# Microcontroller.net
KiCad netlist of a schematic drawn in Altium Designer
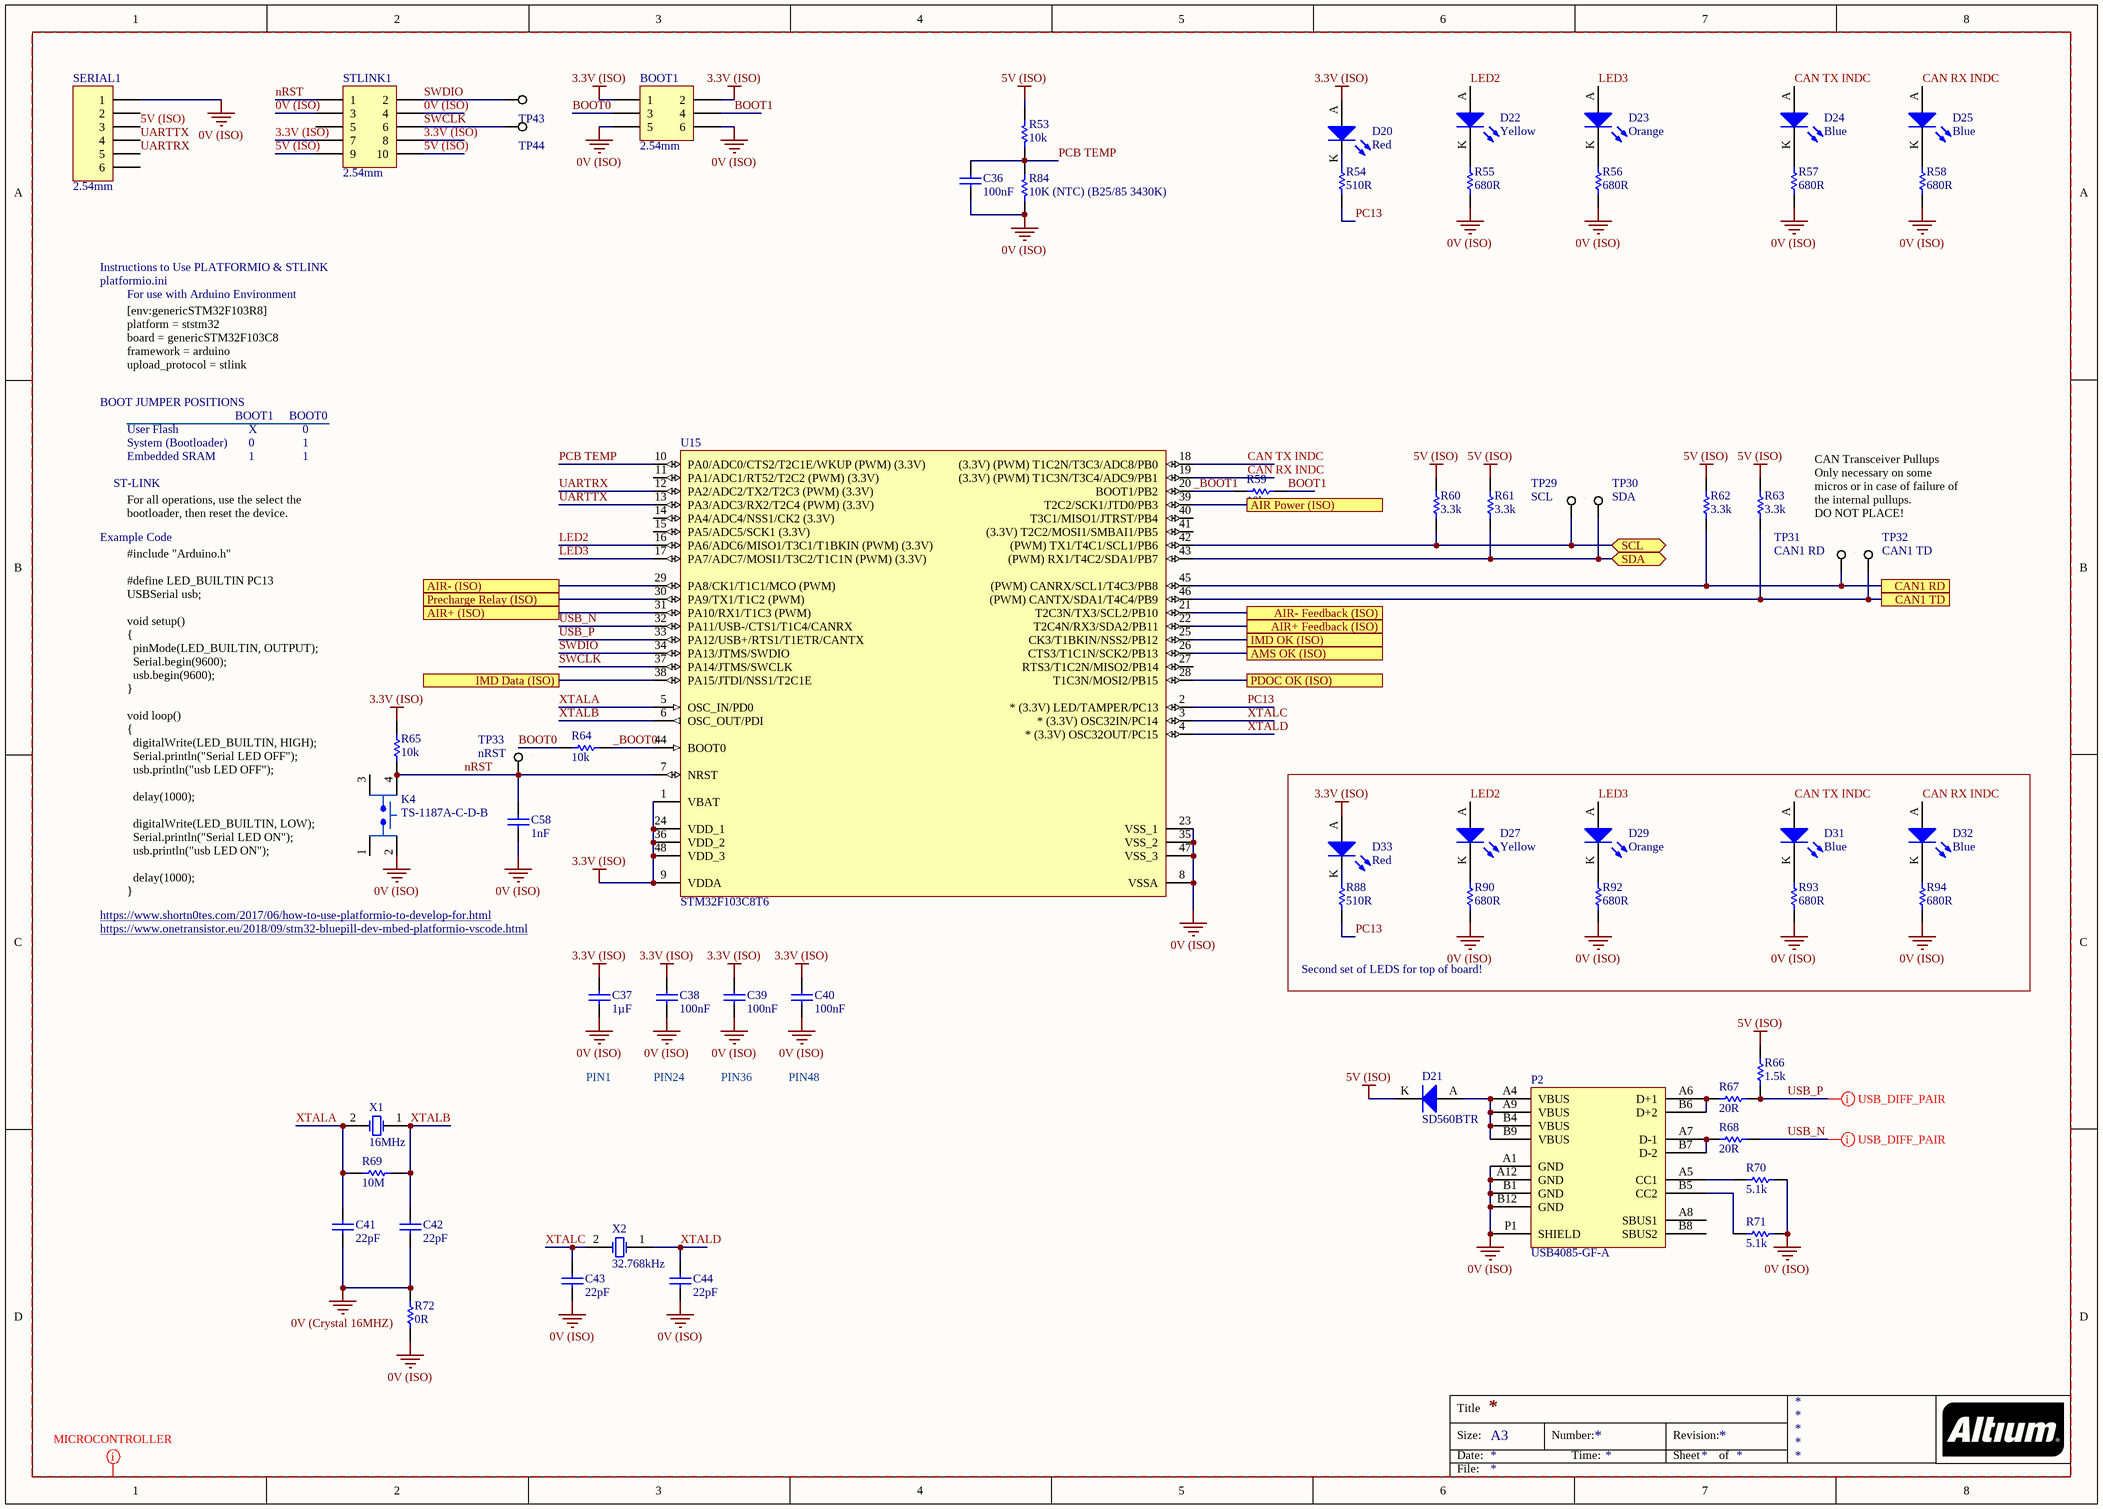
[diagram p0: Microcontroller.SchDoc]

(export (version "E")
  (design (tool "Eeschema 10.0.6"))
  (components
    (comp (ref "BOOT1")
      (value "2.54mm")
      (footprint "TH 2.54mm Header 2x3")
      (fields (field (name "PART NUMBER") "TH 2.54mm Header 2x3") (field (name "CONTACT") "NA"))
      (libsource (lib "ts_20-standard-connectors") (part "Header 2x3"))
    )
    (comp (ref "C36")
      (value "100nF")
      (footprint "0805")
      (fields
        (field (name "PART NUMBER") "GCM21BR71E104KA37L")
        (field (name "TOLERANCE") "10%")
        (field (name "MANUFACTURER") "muRata")
      )
      (libsource (lib "ts_20-standard-library") (part "Capacitor"))
    )
    (comp (ref "C37")
      (value "1µF")
      (footprint "0805")
      (fields
        (field (name "PART NUMBER") "GCM21BR71H105KA03L")
        (field (name "TOLERANCE") "±10%")
        (field (name "MANUFACTURER") "muRata")
      )
      (libsource (lib "ts_20-standard-library") (part "Capacitor"))
    )
    (comp (ref "C38")
      (value "100nF")
      (footprint "0805")
      (fields
        (field (name "PART NUMBER") "GCM21BR71H104KA37L")
        (field (name "TOLERANCE") "±10%")
        (field (name "MANUFACTURER") "muRata")
      )
      (libsource (lib "ts_20-standard-library") (part "Capacitor"))
    )
    (comp (ref "C39")
      (value "100nF")
      (footprint "0805")
      (fields
        (field (name "PART NUMBER") "GCM21BR71H104KA37L")
        (field (name "TOLERANCE") "±10%")
        (field (name "MANUFACTURER") "muRata")
      )
      (libsource (lib "ts_20-standard-library") (part "Capacitor"))
    )
    (comp (ref "C40")
      (value "100nF")
      (footprint "0805")
      (fields
        (field (name "PART NUMBER") "GCM21BR71H104KA37L")
        (field (name "TOLERANCE") "±10%")
        (field (name "MANUFACTURER") "muRata")
      )
      (libsource (lib "ts_20-standard-library") (part "Capacitor"))
    )
    (comp (ref "C41")
      (value "22pF")
      (footprint "0805")
      (fields
        (field (name "PART NUMBER") "GRM21A5C2E220JW01D")
        (field (name "TOLERANCE") "±5%")
        (field (name "MANUFACTURER") "muRata")
      )
      (libsource (lib "ts_20-standard-library") (part "Capacitor"))
    )
    (comp (ref "C42")
      (value "22pF")
      (footprint "0805")
      (fields
        (field (name "PART NUMBER") "GRM21A5C2E220JW01D")
        (field (name "TOLERANCE") "±5%")
        (field (name "MANUFACTURER") "muRata")
      )
      (libsource (lib "ts_20-standard-library") (part "Capacitor"))
    )
    (comp (ref "C43")
      (value "22pF")
      (footprint "0805")
      (fields
        (field (name "PART NUMBER") "GRM21A5C2E220JW01D")
        (field (name "TOLERANCE") "±5%")
        (field (name "MANUFACTURER") "muRata")
      )
      (libsource (lib "ts_20-standard-library") (part "Capacitor"))
    )
    (comp (ref "C44")
      (value "22pF")
      (footprint "0805")
      (fields
        (field (name "PART NUMBER") "GRM21A5C2E220JW01D")
        (field (name "TOLERANCE") "±5%")
        (field (name "MANUFACTURER") "muRata")
      )
      (libsource (lib "ts_20-standard-library") (part "Capacitor"))
    )
    (comp (ref "C58")
      (value "1nF")
      (footprint "0805")
      (fields
        (field (name "PART NUMBER") "GCM21BR71H102KA37L")
        (field (name "TOLERANCE") "10%")
        (field (name "MANUFACTURER") "muRata")
      )
      (libsource (lib "ts_20-standard-library") (part "Capacitor"))
    )
    (comp (ref "D20")
      (value "Red")
      (footprint "0805 LED")
      (description "Red LED Indication - Discrete 1.75V 0805 (2012 Metric)")
      (fields (field (name "MANUFACTURER") "ROHM Semiconductor") (field (name "PART NUMBER") "SML-210LTT86"))
      (libsource (lib "ts_20-standard-library") (part "LED"))
    )
    (comp (ref "D21")
      (value "SD560BTR")
      (footprint "SMB Diode")
      (description "1.2V_F 600V 5A SMB")
      (fields
        (field (name "MANUFACTURER") "SMC Diode Solutions")
        (field (name "DIGIKEY PART NUMBER") "1655-1530-2-ND")
      )
      (libsource (lib "ts_20-standard-library") (part "Diode"))
    )
    (comp (ref "D22")
      (value "Yellow")
      (footprint "0805 LED")
      (description "Yellow LED Indication - Discrete 1.75V 0805 (2012 Metric)")
      (fields (field (name "PART NUMBER") "SML-211YTT86") (field (name "MANUFACTURER") "ROHM Semiconductor"))
      (libsource (lib "ts_20-standard-library") (part "LED"))
    )
    (comp (ref "D23")
      (value "Orange")
      (footprint "0805 LED")
      (description "Orange LED Indication - Discrete 1.75V 0805 (2012 Metric)")
      (fields (field (name "PART NUMBER") "SML-211DTT86") (field (name "MANUFACTURER") "ROHM Semiconductor"))
      (libsource (lib "ts_20-standard-library") (part "LED"))
    )
    (comp (ref "D24")
      (value "Blue")
      (footprint "0805 LED")
      (description "LED BLUE CLEAR 2012 SMD")
      (fields
        (field (name "PART NUMBER") "SML-MN2BCTT86C")
        (field (name "MANUFACTURER") "ROHM Semiconductor")
      )
      (libsource (lib "ts_20-standard-library") (part "LED"))
    )
    (comp (ref "D25")
      (value "Blue")
      (footprint "0805 LED")
      (description "LED BLUE CLEAR 2012 SMD")
      (fields
        (field (name "PART NUMBER") "SML-MN2BCTT86C")
        (field (name "MANUFACTURER") "ROHM Semiconductor")
      )
      (libsource (lib "ts_20-standard-library") (part "LED"))
    )
    (comp (ref "D27")
      (value "Yellow")
      (footprint "0805 LED")
      (description "Yellow LED Indication - Discrete 1.75V 0805 (2012 Metric)")
      (fields (field (name "PART NUMBER") "SML-211YTT86") (field (name "MANUFACTURER") "ROHM Semiconductor"))
      (libsource (lib "ts_20-standard-library") (part "LED"))
    )
    (comp (ref "D29")
      (value "Orange")
      (footprint "0805 LED")
      (description "Orange LED Indication - Discrete 1.75V 0805 (2012 Metric)")
      (fields (field (name "PART NUMBER") "SML-211DTT86") (field (name "MANUFACTURER") "ROHM Semiconductor"))
      (libsource (lib "ts_20-standard-library") (part "LED"))
    )
    (comp (ref "D31")
      (value "Blue")
      (footprint "0805 LED")
      (description "LED BLUE CLEAR 2012 SMD")
      (fields
        (field (name "PART NUMBER") "SML-MN2BCTT86C")
        (field (name "MANUFACTURER") "ROHM Semiconductor")
      )
      (libsource (lib "ts_20-standard-library") (part "LED"))
    )
    (comp (ref "D32")
      (value "Blue")
      (footprint "0805 LED")
      (description "LED BLUE CLEAR 2012 SMD")
      (fields
        (field (name "PART NUMBER") "SML-MN2BCTT86C")
        (field (name "MANUFACTURER") "ROHM Semiconductor")
      )
      (libsource (lib "ts_20-standard-library") (part "LED"))
    )
    (comp (ref "D33")
      (value "Red")
      (footprint "0805 LED")
      (description "Red LED Indication - Discrete 1.75V 0805 (2012 Metric)")
      (fields (field (name "MANUFACTURER") "ROHM Semiconductor") (field (name "PART NUMBER") "SML-210LTT86"))
      (libsource (lib "ts_20-standard-library") (part "LED"))
    )
    (comp (ref "K4")
      (value "TS-1187A-C-D-B")
      (footprint "XKB SW-4.5")
      (description "TACTILE SWITCHES SPST 5.10MM X 5.10MM 0.80MM SMD ROHS")
      (fields (field (name "MANUFACTURER") "XKB Enerprise"))
      (libsource (lib "ts_20-standard-library") (part "SPST (Mom) Push Button"))
    )
    (comp (ref "P2")
      (value "USB4085-GF-A")
      (footprint "USB4085-GF-A")
      (description "USB - C (Type - C) USB 2.0 Receptacle Connector 16 Position Through Hole, Right Angle")
      (fields (field (name "DIGIKEY PART NUMBER") "2073-USB4085-GF-ACT-ND"))
      (libsource (lib "ts_20-standard-connectors") (part "USB4085-GF-A"))
    )
    (comp (ref "R53")
      (value "10k")
      (footprint "0805")
      (fields
        (field (name "PART NUMBER") "RC0805FR0710KL")
        (field (name "MANUFACTURER") "YAGEO")
        (field (name "TOLERANCE") "0.01")
      )
      (libsource (lib "ts_20-standard-library") (part "Resistor"))
    )
    (comp (ref "R54")
      (value "510R")
      (footprint "0805")
      (fields
        (field (name "MANUFACTURER") "YAGEO")
        (field (name "PART NUMBER") "RC0805FR07510RL")
        (field (name "TOLERANCE") "0.01")
      )
      (libsource (lib "ts_20-standard-library") (part "Resistor"))
    )
    (comp (ref "R55")
      (value "680R")
      (footprint "0805")
      (fields
        (field (name "PART NUMBER") "RC0805FR07680RL")
        (field (name "MANUFACTURER") "YAGEO")
        (field (name "TOLERANCE") "0.01")
      )
      (libsource (lib "ts_20-standard-library") (part "Resistor"))
    )
    (comp (ref "R56")
      (value "680R")
      (footprint "0805")
      (fields
        (field (name "PART NUMBER") "RC0805FR07680RL")
        (field (name "MANUFACTURER") "YAGEO")
        (field (name "TOLERANCE") "0.01")
      )
      (libsource (lib "ts_20-standard-library") (part "Resistor"))
    )
    (comp (ref "R57")
      (value "680R")
      (footprint "0805")
      (fields
        (field (name "PART NUMBER") "RC0805FR07680RL")
        (field (name "MANUFACTURER") "YAGEO")
        (field (name "TOLERANCE") "0.01")
      )
      (libsource (lib "ts_20-standard-library") (part "Resistor"))
    )
    (comp (ref "R58")
      (value "680R")
      (footprint "0805")
      (fields
        (field (name "PART NUMBER") "RC0805FR07680RL")
        (field (name "MANUFACTURER") "YAGEO")
        (field (name "TOLERANCE") "0.01")
      )
      (libsource (lib "ts_20-standard-library") (part "Resistor"))
    )
    (comp (ref "R59")
      (value "10k")
      (footprint "0805")
      (fields
        (field (name "PART NUMBER") "RC0805FR0710KL")
        (field (name "MANUFACTURER") "YAGEO")
        (field (name "TOLERANCE") "0.01")
      )
      (libsource (lib "ts_20-standard-library") (part "Resistor"))
    )
    (comp (ref "R60")
      (value "3.3k")
      (footprint "0805")
      (fields
        (field (name "PART NUMBER") "RC0805FR073K3L")
        (field (name "MANUFACTURER") "YAGEO")
        (field (name "TOLERANCE") "0.01")
      )
      (libsource (lib "ts_20-standard-library") (part "Resistor"))
    )
    (comp (ref "R61")
      (value "3.3k")
      (footprint "0805")
      (fields
        (field (name "PART NUMBER") "RC0805FR073K3L")
        (field (name "MANUFACTURER") "YAGEO")
        (field (name "TOLERANCE") "0.01")
      )
      (libsource (lib "ts_20-standard-library") (part "Resistor"))
    )
    (comp (ref "R62")
      (value "3.3k")
      (footprint "0805")
      (fields
        (field (name "PART NUMBER") "RC0805FR073K3L")
        (field (name "MANUFACTURER") "YAGEO")
        (field (name "TOLERANCE") "0.01")
      )
      (libsource (lib "ts_20-standard-library") (part "Resistor"))
    )
    (comp (ref "R63")
      (value "3.3k")
      (footprint "0805")
      (fields
        (field (name "PART NUMBER") "RC0805FR073K3L")
        (field (name "MANUFACTURER") "YAGEO")
        (field (name "TOLERANCE") "0.01")
      )
      (libsource (lib "ts_20-standard-library") (part "Resistor"))
    )
    (comp (ref "R64")
      (value "10k")
      (footprint "0805")
      (fields
        (field (name "PART NUMBER") "RC0805FR0710KL")
        (field (name "MANUFACTURER") "YAGEO")
        (field (name "TOLERANCE") "0.01")
      )
      (libsource (lib "ts_20-standard-library") (part "Resistor"))
    )
    (comp (ref "R65")
      (value "10k")
      (footprint "0805")
      (fields
        (field (name "MANUFACTURER") "YAGEO")
        (field (name "PART NUMBER") "RC0805FR0710KL")
        (field (name "TOLERANCE") "0.01")
      )
      (libsource (lib "ts_20-standard-library") (part "Resistor"))
    )
    (comp (ref "R66")
      (value "1.5k")
      (footprint "0805")
      (fields
        (field (name "PART NUMBER") "RC0805FR071K5L")
        (field (name "MANUFACTURER") "YAGEO")
        (field (name "TOLERANCE") "0.01")
      )
      (libsource (lib "ts_20-standard-library") (part "Resistor"))
    )
    (comp (ref "R67")
      (value "20R")
      (footprint "0805")
      (fields
        (field (name "PART NUMBER") "RC0805FR0720RL")
        (field (name "MANUFACTURER") "YAGEO")
        (field (name "TOLERANCE") "0.01")
      )
      (libsource (lib "ts_20-standard-library") (part "Resistor"))
    )
    (comp (ref "R68")
      (value "20R")
      (footprint "0805")
      (fields
        (field (name "PART NUMBER") "RC0805FR0720RL")
        (field (name "MANUFACTURER") "YAGEO")
        (field (name "TOLERANCE") "0.01")
      )
      (libsource (lib "ts_20-standard-library") (part "Resistor"))
    )
    (comp (ref "R69")
      (value "10M")
      (footprint "0805")
      (fields
        (field (name "PART NUMBER") "RC0805FR0710ML")
        (field (name "MANUFACTURER") "YAGEO")
        (field (name "TOLERANCE") "0.01")
      )
      (libsource (lib "ts_20-standard-library") (part "Resistor"))
    )
    (comp (ref "R70")
      (value "5.1k")
      (footprint "0805")
      (fields
        (field (name "PART NUMBER") "RC0805FR075K1L")
        (field (name "MANUFACTURER") "YAGEO")
        (field (name "TOLERANCE") "0.01")
      )
      (libsource (lib "ts_20-standard-library") (part "Resistor"))
    )
    (comp (ref "R71")
      (value "5.1k")
      (footprint "0805")
      (fields
        (field (name "PART NUMBER") "RC0805FR075K1L")
        (field (name "MANUFACTURER") "YAGEO")
        (field (name "TOLERANCE") "0.01")
      )
      (libsource (lib "ts_20-standard-library") (part "Resistor"))
    )
    (comp (ref "R72")
      (value "0R")
      (footprint "0805")
      (fields
        (field (name "PART NUMBER") "RC0805FR070RL")
        (field (name "MANUFACTURER") "YAGEO")
        (field (name "TOLERANCE") "0.01")
      )
      (libsource (lib "ts_20-standard-library") (part "Resistor"))
    )
    (comp (ref "R84")
      (value "10K (NTC) (B25/85 3430K)")
      (footprint "0805")
      (fields
        (field (name "PART NUMBER") "NTCS0805E3103FLT")
        (field (name "MANUFACTURER") "Vishay Beyschlag")
        (field (name "TOLERANCE") "0.01")
      )
      (libsource (lib "ts_20-standard-library") (part "Resistor"))
    )
    (comp (ref "R88")
      (value "510R")
      (footprint "0805")
      (fields
        (field (name "MANUFACTURER") "YAGEO")
        (field (name "PART NUMBER") "RC0805FR07510RL")
        (field (name "TOLERANCE") "0.01")
      )
      (libsource (lib "ts_20-standard-library") (part "Resistor"))
    )
    (comp (ref "R90")
      (value "680R")
      (footprint "0805")
      (fields
        (field (name "PART NUMBER") "RC0805FR07680RL")
        (field (name "MANUFACTURER") "YAGEO")
        (field (name "TOLERANCE") "0.01")
      )
      (libsource (lib "ts_20-standard-library") (part "Resistor"))
    )
    (comp (ref "R92")
      (value "680R")
      (footprint "0805")
      (fields
        (field (name "PART NUMBER") "RC0805FR07680RL")
        (field (name "MANUFACTURER") "YAGEO")
        (field (name "TOLERANCE") "0.01")
      )
      (libsource (lib "ts_20-standard-library") (part "Resistor"))
    )
    (comp (ref "R93")
      (value "680R")
      (footprint "0805")
      (fields
        (field (name "PART NUMBER") "RC0805FR07680RL")
        (field (name "MANUFACTURER") "YAGEO")
        (field (name "TOLERANCE") "0.01")
      )
      (libsource (lib "ts_20-standard-library") (part "Resistor"))
    )
    (comp (ref "R94")
      (value "680R")
      (footprint "0805")
      (fields
        (field (name "PART NUMBER") "RC0805FR07680RL")
        (field (name "MANUFACTURER") "YAGEO")
        (field (name "TOLERANCE") "0.01")
      )
      (libsource (lib "ts_20-standard-library") (part "Resistor"))
    )
    (comp (ref "SERIAL1")
      (value "2.54mm")
      (footprint "TH 2.54mm Header 1x6")
      (fields (field (name "PART NUMBER") "TH 2.54mm Header 1x6") (field (name "CONTACT") "NA"))
      (libsource (lib "ts_20-standard-connectors") (part "Header 1x6"))
    )
    (comp (ref "STLINK1")
      (value "2.54mm")
      (footprint "TH 2.54mm Header 2x5")
      (fields (field (name "PART NUMBER") "TH 2.54mm Header 2x5") (field (name "CONTACT") "NA"))
      (libsource (lib "ts_20-standard-connectors") (part "Header 2x5"))
    )
    (comp (ref "TP29")
      (value "SCL")
      (footprint "SMD Test Point 1mm")
      (fields (field (name "PART NUMBER") "SMD Test Point Small") (field (name "CONTACT") "NA"))
      (libsource (lib "ts_20-standard-connectors") (part "Test Point Small"))
    )
    (comp (ref "TP30")
      (value "SDA")
      (footprint "SMD Test Point 1mm")
      (fields (field (name "PART NUMBER") "SMD Test Point Small") (field (name "CONTACT") "NA"))
      (libsource (lib "ts_20-standard-connectors") (part "Test Point Small"))
    )
    (comp (ref "TP31")
      (value "CAN1 RD")
      (footprint "SMD Test Point 1mm")
      (fields (field (name "PART NUMBER") "SMD Test Point Small") (field (name "CONTACT") "NA"))
      (libsource (lib "ts_20-standard-connectors") (part "Test Point Small"))
    )
    (comp (ref "TP32")
      (value "CAN1 TD")
      (footprint "SMD Test Point 1mm")
      (fields (field (name "PART NUMBER") "SMD Test Point Small") (field (name "CONTACT") "NA"))
      (libsource (lib "ts_20-standard-connectors") (part "Test Point Small"))
    )
    (comp (ref "TP33")
      (value "nRST")
      (footprint "SMD Test Point 1mm")
      (fields (field (name "PART NUMBER") "SMD Test Point Small") (field (name "CONTACT") "NA"))
      (libsource (lib "ts_20-standard-connectors") (part "Test Point Small"))
    )
    (comp (ref "TP43")
      (value "0mm")
      (footprint "SMD Test Point 1mm")
      (fields (field (name "PART NUMBER") "SMD Test Point Small") (field (name "CONTACT") "NA"))
      (libsource (lib "ts_20-standard-connectors") (part "Test Point Small"))
    )
    (comp (ref "TP44")
      (value "0mm")
      (footprint "SMD Test Point 1mm")
      (fields (field (name "PART NUMBER") "SMD Test Point Small") (field (name "CONTACT") "NA"))
      (libsource (lib "ts_20-standard-connectors") (part "Test Point Small"))
    )
    (comp (ref "U15")
      (value "STM32F103C8T6")
      (footprint "STM 48-LQFP")
      (description "ARM® Cortex®-M3 STM32F1 Microcontroller IC 32-Bit 72MHz 64KB (64K x 8) FLASH")
      (fields
        (field (name "MANUFACTURER") "STMicroelectronics")
        (field (name "DIGIKEY PART NUMBER") "497-6063-ND")
      )
      (libsource (lib "ts_20-standard-library") (part "STM32F103C8T6"))
    )
    (comp (ref "X1")
      (value "16MHz")
      (footprint "Abracon HC-49/US")
      (fields
        (field (name "PART NUMBER") "ABLS-16.000MHZ-B4-T")
        (field (name "MANUFACTURER") "Abracon LLC")
        (field (name "DIGIKEY PART NUMBER") "535-10226-1-ND")
      )
      (libsource (lib "ts_20-standard-library") (part "Crystal"))
    )
    (comp (ref "X2")
      (value "32.768kHz")
      (footprint "EPSON 2-SMD")
      (fields
        (field (name "PART NUMBER") "FC-135 32.7680KA-A5")
        (field (name "MANUFACTURER") "EPSON")
        (field (name "DIGIKEY PART NUMBER") "SER4103TR-ND")
      )
      (libsource (lib "ts_20-standard-library") (part "Crystal"))
    )
  )
  (nets
    (net (code "1") (name "/AIR Power (ISO)") (class "Default")
      (node (ref "U15") (pin "39") (pinfunction "T2C2/SCK1/JTD0/PB3_39") (pintype "bidirectional"))
    )
    (net (code "2") (name "/AIR+ (ISO)") (class "Default")
      (node (ref "U15") (pin "31") (pinfunction "PA10/RX1/T1C3_(PWM)_31") (pintype "bidirectional"))
    )
    (net (code "3") (name "/AIR+ Feedback (ISO)") (class "Default")
      (node (ref "U15") (pin "22") (pinfunction "T2C4N/RX3/SDA2/PB11_22") (pintype "bidirectional"))
    )
    (net (code "4") (name "/AIR- (ISO)") (class "Default")
      (node (ref "U15") (pin "29") (pinfunction "PA8/CK1/T1C1/MCO_(PWM)_29") (pintype "bidirectional"))
    )
    (net (code "5") (name "/AIR- Feedback (ISO)") (class "Default")
      (node (ref "U15") (pin "21") (pinfunction "T2C3N/TX3/SCL2/PB10_21") (pintype "bidirectional"))
    )
    (net (code "6") (name "/AMS OK (ISO)") (class "Default")
      (node (ref "U15") (pin "26") (pinfunction "CTS3/T1C1N/SCK2/PB13_26") (pintype "bidirectional"))
    )
    (net (code "7") (name "/BOOT0") (class "Default")
      (node (ref "BOOT1") (pin "3") (pinfunction "3_3") (pintype "passive"))
      (node (ref "R64") (pin "1") (pinfunction "1_1") (pintype "passive"))
    )
    (net (code "8") (name "/BOOT1") (class "Default")
      (node (ref "BOOT1") (pin "4") (pinfunction "4_4") (pintype "passive"))
      (node (ref "R59") (pin "2") (pinfunction "2_2") (pintype "passive"))
    )
    (net (code "9") (name "/CAN RX INDC") (class "Default")
      (node (ref "D25") (pin "A") (pinfunction "A_A") (pintype "passive"))
      (node (ref "D32") (pin "A") (pinfunction "A_A") (pintype "passive"))
      (node (ref "U15") (pin "19") (pinfunction "(3.3V)_(PWM)_T1C3N/T3C4/ADC9/PB1_19") (pintype "bidirectional"))
    )
    (net (code "10") (name "/CAN TX INDC") (class "Default")
      (node (ref "D24") (pin "A") (pinfunction "A_A") (pintype "passive"))
      (node (ref "D31") (pin "A") (pinfunction "A_A") (pintype "passive"))
      (node (ref "U15") (pin "18") (pinfunction "(3.3V)_(PWM)_T1C2N/T3C3/ADC8/PB0_18") (pintype "bidirectional"))
    )
    (net (code "11") (name "/CAN1 RD") (class "Default")
      (node (ref "R62") (pin "1") (pinfunction "1_1") (pintype "passive"))
      (node (ref "TP31") (pin "1") (pinfunction "1_1") (pintype "passive"))
      (node (ref "U15") (pin "45") (pinfunction "(PWM)_CANRX/SCL1/T4C3/PB8_45") (pintype "bidirectional"))
    )
    (net (code "12") (name "/CAN1 TD") (class "Default")
      (node (ref "R63") (pin "1") (pinfunction "1_1") (pintype "passive"))
      (node (ref "TP32") (pin "1") (pinfunction "1_1") (pintype "passive"))
      (node (ref "U15") (pin "46") (pinfunction "(PWM)_CANTX/SDA1/T4C4/PB9_46") (pintype "bidirectional"))
    )
    (net (code "13") (name "/IMD Data (ISO)") (class "Default")
      (node (ref "U15") (pin "38") (pinfunction "PA15/JTDI/NSS1/T2C1E_38") (pintype "bidirectional"))
    )
    (net (code "14") (name "/IMD OK (ISO)") (class "Default")
      (node (ref "U15") (pin "25") (pinfunction "CK3/T1BKIN/NSS2/PB12_25") (pintype "bidirectional"))
    )
    (net (code "15") (name "/LED2") (class "Default")
      (node (ref "D22") (pin "A") (pinfunction "A_A") (pintype "passive"))
      (node (ref "D27") (pin "A") (pinfunction "A_A") (pintype "passive"))
      (node (ref "U15") (pin "16") (pinfunction "PA6/ADC6/MISO1/T3C1/T1BKIN_(PWM)_(3.3V)_16") (pintype "bidirectional"))
    )
    (net (code "16") (name "/LED3") (class "Default")
      (node (ref "D23") (pin "A") (pinfunction "A_A") (pintype "passive"))
      (node (ref "D29") (pin "A") (pinfunction "A_A") (pintype "passive"))
      (node (ref "U15") (pin "17") (pinfunction "PA7/ADC7/MOSI1/T3C2/T1C1N_(PWM)_(3.3V)_17") (pintype "bidirectional"))
    )
    (net (code "17") (name "/PC13") (class "Default")
      (node (ref "R54") (pin "1") (pinfunction "1_1") (pintype "passive"))
      (node (ref "R88") (pin "1") (pinfunction "1_1") (pintype "passive"))
      (node (ref "U15") (pin "2") (pinfunction "*_(3.3V)_LED/TAMPER/PC13_2") (pintype "bidirectional"))
    )
    (net (code "18") (name "/PCB TEMP") (class "Default")
      (node (ref "C36") (pin "2") (pinfunction "2_2") (pintype "passive"))
      (node (ref "R53") (pin "1") (pinfunction "1_1") (pintype "passive"))
      (node (ref "R84") (pin "2") (pinfunction "2_2") (pintype "passive"))
      (node (ref "U15") (pin "10") (pinfunction "PA0/ADC0/CTS2/T2C1E/WKUP_(PWM)_(3.3V)_10") (pintype "bidirectional"))
    )
    (net (code "19") (name "/PDOC OK (ISO)") (class "Default")
      (node (ref "U15") (pin "28") (pinfunction "T1C3N/MOSI2/PB15_28") (pintype "bidirectional"))
    )
    (net (code "20") (name "/Precharge Relay (ISO)") (class "Default")
      (node (ref "U15") (pin "30") (pinfunction "PA9/TX1/T1C2_(PWM)_30") (pintype "bidirectional"))
    )
    (net (code "21") (name "/SCL") (class "Default")
      (node (ref "R60") (pin "1") (pinfunction "1_1") (pintype "passive"))
      (node (ref "TP29") (pin "1") (pinfunction "1_1") (pintype "passive"))
      (node (ref "U15") (pin "42") (pinfunction "(PWM)_TX1/T4C1/SCL1/PB6_42") (pintype "bidirectional"))
    )
    (net (code "22") (name "/SDA") (class "Default")
      (node (ref "R61") (pin "1") (pinfunction "1_1") (pintype "passive"))
      (node (ref "TP30") (pin "1") (pinfunction "1_1") (pintype "passive"))
      (node (ref "U15") (pin "43") (pinfunction "(PWM)_RX1/T4C2/SDA1/PB7_43") (pintype "bidirectional"))
    )
    (net (code "23") (name "/SWCLK") (class "Default")
      (node (ref "STLINK1") (pin "6") (pinfunction "6_6") (pintype "passive"))
      (node (ref "TP44") (pin "1") (pinfunction "1_1") (pintype "passive"))
      (node (ref "U15") (pin "37") (pinfunction "PA14/JTMS/SWCLK_37") (pintype "bidirectional"))
    )
    (net (code "24") (name "/SWDIO") (class "Default")
      (node (ref "STLINK1") (pin "2") (pinfunction "2_2") (pintype "passive"))
      (node (ref "TP43") (pin "1") (pinfunction "1_1") (pintype "passive"))
      (node (ref "U15") (pin "34") (pinfunction "PA13/JTMS/SWDIO_34") (pintype "bidirectional"))
    )
    (net (code "25") (name "/UARTRX") (class "Default")
      (node (ref "SERIAL1") (pin "5") (pinfunction "5_5") (pintype "passive"))
      (node (ref "U15") (pin "12") (pinfunction "PA2/ADC2/TX2/T2C3_(PWM)_(3.3V)_12") (pintype "bidirectional"))
    )
    (net (code "26") (name "/UARTTX") (class "Default")
      (node (ref "SERIAL1") (pin "4") (pinfunction "4_4") (pintype "passive"))
      (node (ref "U15") (pin "13") (pinfunction "PA3/ADC3/RX2/T2C4_(PWM)_(3.3V)_13") (pintype "bidirectional"))
    )
    (net (code "27") (name "/USB_N") (class "Default")
      (node (ref "R68") (pin "2") (pinfunction "2_2") (pintype "passive"))
      (node (ref "U15") (pin "32") (pinfunction "PA11/USB-/CTS1/T1C4/CANRX_32") (pintype "bidirectional"))
    )
    (net (code "28") (name "/USB_P") (class "Default")
      (node (ref "R66") (pin "1") (pinfunction "1_1") (pintype "passive"))
      (node (ref "R67") (pin "2") (pinfunction "2_2") (pintype "passive"))
      (node (ref "U15") (pin "33") (pinfunction "PA12/USB+/RTS1/T1ETR/CANTX_33") (pintype "bidirectional"))
    )
    (net (code "29") (name "/XTALA") (class "Default")
      (node (ref "C41") (pin "2") (pinfunction "2_2") (pintype "passive"))
      (node (ref "R69") (pin "2") (pinfunction "2_2") (pintype "passive"))
      (node (ref "U15") (pin "5") (pinfunction "OSC_IN/PD0_5") (pintype "input"))
      (node (ref "X1") (pin "2") (pinfunction "OSC2_2") (pintype "passive"))
    )
    (net (code "30") (name "/XTALB") (class "Default")
      (node (ref "C42") (pin "2") (pinfunction "2_2") (pintype "passive"))
      (node (ref "R69") (pin "1") (pinfunction "1_1") (pintype "passive"))
      (node (ref "U15") (pin "6") (pinfunction "OSC_OUT/PDI_6") (pintype "output"))
      (node (ref "X1") (pin "1") (pinfunction "OSC1_1") (pintype "passive"))
    )
    (net (code "31") (name "/XTALC") (class "Default")
      (node (ref "C43") (pin "2") (pinfunction "2_2") (pintype "passive"))
      (node (ref "U15") (pin "3") (pinfunction "*_(3.3V)_OSC32IN/PC14_3") (pintype "bidirectional"))
      (node (ref "X2") (pin "2") (pinfunction "OSC2_2") (pintype "passive"))
    )
    (net (code "32") (name "/XTALD") (class "Default")
      (node (ref "C44") (pin "2") (pinfunction "2_2") (pintype "passive"))
      (node (ref "U15") (pin "4") (pinfunction "*_(3.3V)_OSC32OUT/PC15_4") (pintype "bidirectional"))
      (node (ref "X2") (pin "1") (pinfunction "OSC1_1") (pintype "passive"))
    )
    (net (code "33") (name "/_BOOT0") (class "Default")
      (node (ref "R64") (pin "2") (pinfunction "2_2") (pintype "passive"))
      (node (ref "U15") (pin "44") (pinfunction "BOOT0_44") (pintype "input"))
    )
    (net (code "34") (name "/_BOOT1") (class "Default")
      (node (ref "R59") (pin "1") (pinfunction "1_1") (pintype "passive"))
      (node (ref "U15") (pin "20") (pinfunction "BOOT1/PB2_20") (pintype "bidirectional"))
    )
    (net (code "35") (name "/nRST") (class "Default")
      (node (ref "C58") (pin "2") (pinfunction "2_2") (pintype "passive"))
      (node (ref "K4") (pin "4") (pinfunction "VDD_4") (pintype "passive"))
      (node (ref "R65") (pin "1") (pinfunction "1_1") (pintype "passive"))
      (node (ref "STLINK1") (pin "1") (pinfunction "1_1") (pintype "passive"))
      (node (ref "TP33") (pin "1") (pinfunction "1_1") (pintype "passive"))
      (node (ref "U15") (pin "7") (pinfunction "NRST_7") (pintype "bidirectional"))
    )
    (net (code "36") (name "0V (Crystal 16MHZ)") (class "Default")
      (node (ref "C41") (pin "1") (pinfunction "1_1") (pintype "passive"))
      (node (ref "C42") (pin "1") (pinfunction "1_1") (pintype "passive"))
      (node (ref "R72") (pin "2") (pinfunction "2_2") (pintype "passive"))
    )
    (net (code "37") (name "0V (ISO)") (class "Default")
      (node (ref "BOOT1") (pin "5") (pinfunction "5_5") (pintype "passive"))
      (node (ref "BOOT1") (pin "6") (pinfunction "6_6") (pintype "passive"))
      (node (ref "C36") (pin "1") (pinfunction "1_1") (pintype "passive"))
      (node (ref "C37") (pin "1") (pinfunction "1_1") (pintype "passive"))
      (node (ref "C38") (pin "1") (pinfunction "1_1") (pintype "passive"))
      (node (ref "C39") (pin "1") (pinfunction "1_1") (pintype "passive"))
      (node (ref "C40") (pin "1") (pinfunction "1_1") (pintype "passive"))
      (node (ref "C43") (pin "1") (pinfunction "1_1") (pintype "passive"))
      (node (ref "C44") (pin "1") (pinfunction "1_1") (pintype "passive"))
      (node (ref "C58") (pin "1") (pinfunction "1_1") (pintype "passive"))
      (node (ref "K4") (pin "2") (pinfunction "VDD_2") (pintype "passive"))
      (node (ref "P2") (pin "A1") (pinfunction "GND_A1") (pintype "passive"))
      (node (ref "P2") (pin "A12") (pinfunction "GND_A12") (pintype "passive"))
      (node (ref "P2") (pin "B1") (pinfunction "GND_B1") (pintype "passive"))
      (node (ref "P2") (pin "B12") (pinfunction "GND_B12") (pintype "passive"))
      (node (ref "P2") (pin "P1") (pinfunction "SHIELD_P1") (pintype "passive"))
      (node (ref "R55") (pin "1") (pinfunction "1_1") (pintype "passive"))
      (node (ref "R56") (pin "1") (pinfunction "1_1") (pintype "passive"))
      (node (ref "R57") (pin "1") (pinfunction "1_1") (pintype "passive"))
      (node (ref "R58") (pin "1") (pinfunction "1_1") (pintype "passive"))
      (node (ref "R70") (pin "2") (pinfunction "2_2") (pintype "passive"))
      (node (ref "R71") (pin "2") (pinfunction "2_2") (pintype "passive"))
      (node (ref "R72") (pin "1") (pinfunction "1_1") (pintype "passive"))
      (node (ref "R84") (pin "1") (pinfunction "1_1") (pintype "passive"))
      (node (ref "R90") (pin "1") (pinfunction "1_1") (pintype "passive"))
      (node (ref "R92") (pin "1") (pinfunction "1_1") (pintype "passive"))
      (node (ref "R93") (pin "1") (pinfunction "1_1") (pintype "passive"))
      (node (ref "R94") (pin "1") (pinfunction "1_1") (pintype "passive"))
      (node (ref "SERIAL1") (pin "1") (pinfunction "1_1") (pintype "passive"))
      (node (ref "STLINK1") (pin "3") (pinfunction "3_3") (pintype "passive"))
      (node (ref "STLINK1") (pin "4") (pinfunction "4_4") (pintype "passive"))
      (node (ref "U15") (pin "23") (pinfunction "VSS_1_23") (pintype "power_in"))
      (node (ref "U15") (pin "35") (pinfunction "VSS_2_35") (pintype "power_in"))
      (node (ref "U15") (pin "47") (pinfunction "VSS_3_47") (pintype "power_in"))
      (node (ref "U15") (pin "8") (pinfunction "VSSA_8") (pintype "power_in"))
    )
    (net (code "38") (name "3.3V (ISO)") (class "Default")
      (node (ref "BOOT1") (pin "1") (pinfunction "1_1") (pintype "passive"))
      (node (ref "BOOT1") (pin "2") (pinfunction "2_2") (pintype "passive"))
      (node (ref "C37") (pin "2") (pinfunction "2_2") (pintype "passive"))
      (node (ref "C38") (pin "2") (pinfunction "2_2") (pintype "passive"))
      (node (ref "C39") (pin "2") (pinfunction "2_2") (pintype "passive"))
      (node (ref "C40") (pin "2") (pinfunction "2_2") (pintype "passive"))
      (node (ref "D20") (pin "A") (pinfunction "A_A") (pintype "passive"))
      (node (ref "D33") (pin "A") (pinfunction "A_A") (pintype "passive"))
      (node (ref "R65") (pin "2") (pinfunction "2_2") (pintype "passive"))
      (node (ref "STLINK1") (pin "7") (pinfunction "7_7") (pintype "passive"))
      (node (ref "STLINK1") (pin "8") (pinfunction "8_8") (pintype "passive"))
      (node (ref "U15") (pin "1") (pinfunction "VBAT_1") (pintype "power_in"))
      (node (ref "U15") (pin "24") (pinfunction "VDD_1_24") (pintype "power_in"))
      (node (ref "U15") (pin "36") (pinfunction "VDD_2_36") (pintype "power_in"))
      (node (ref "U15") (pin "48") (pinfunction "VDD_3_48") (pintype "power_in"))
      (node (ref "U15") (pin "9") (pinfunction "VDDA_9") (pintype "power_in"))
    )
    (net (code "39") (name "5V (ISO)") (class "Default")
      (node (ref "D21") (pin "K") (pinfunction "K_K") (pintype "passive"))
      (node (ref "R53") (pin "2") (pinfunction "2_2") (pintype "passive"))
      (node (ref "R60") (pin "2") (pinfunction "2_2") (pintype "passive"))
      (node (ref "R61") (pin "2") (pinfunction "2_2") (pintype "passive"))
      (node (ref "R62") (pin "2") (pinfunction "2_2") (pintype "passive"))
      (node (ref "R63") (pin "2") (pinfunction "2_2") (pintype "passive"))
      (node (ref "R66") (pin "2") (pinfunction "2_2") (pintype "passive"))
      (node (ref "SERIAL1") (pin "3") (pinfunction "3_3") (pintype "passive"))
      (node (ref "STLINK1") (pin "10") (pinfunction "10_10") (pintype "passive"))
      (node (ref "STLINK1") (pin "9") (pinfunction "9_9") (pintype "passive"))
    )
    (net (code "40") (name "Net-(D20-PadK)") (class "Default")
      (node (ref "D20") (pin "K") (pinfunction "K_K") (pintype "passive"))
      (node (ref "R54") (pin "2") (pinfunction "2_2") (pintype "passive"))
    )
    (net (code "41") (name "Net-(D21-PadA)") (class "Default")
      (node (ref "D21") (pin "A") (pinfunction "A_A") (pintype "passive"))
      (node (ref "P2") (pin "A4") (pinfunction "VBUS_A4") (pintype "passive"))
      (node (ref "P2") (pin "A9") (pinfunction "VBUS_A9") (pintype "passive"))
      (node (ref "P2") (pin "B4") (pinfunction "VBUS_B4") (pintype "passive"))
      (node (ref "P2") (pin "B9") (pinfunction "VBUS_B9") (pintype "passive"))
    )
    (net (code "42") (name "Net-(D22-PadK)") (class "Default")
      (node (ref "D22") (pin "K") (pinfunction "K_K") (pintype "passive"))
      (node (ref "R55") (pin "2") (pinfunction "2_2") (pintype "passive"))
    )
    (net (code "43") (name "Net-(D23-PadK)") (class "Default")
      (node (ref "D23") (pin "K") (pinfunction "K_K") (pintype "passive"))
      (node (ref "R56") (pin "2") (pinfunction "2_2") (pintype "passive"))
    )
    (net (code "44") (name "Net-(D24-PadK)") (class "Default")
      (node (ref "D24") (pin "K") (pinfunction "K_K") (pintype "passive"))
      (node (ref "R57") (pin "2") (pinfunction "2_2") (pintype "passive"))
    )
    (net (code "45") (name "Net-(D25-PadK)") (class "Default")
      (node (ref "D25") (pin "K") (pinfunction "K_K") (pintype "passive"))
      (node (ref "R58") (pin "2") (pinfunction "2_2") (pintype "passive"))
    )
    (net (code "46") (name "Net-(D27-PadK)") (class "Default")
      (node (ref "D27") (pin "K") (pinfunction "K_K") (pintype "passive"))
      (node (ref "R90") (pin "2") (pinfunction "2_2") (pintype "passive"))
    )
    (net (code "47") (name "Net-(D29-PadK)") (class "Default")
      (node (ref "D29") (pin "K") (pinfunction "K_K") (pintype "passive"))
      (node (ref "R92") (pin "2") (pinfunction "2_2") (pintype "passive"))
    )
    (net (code "48") (name "Net-(D31-PadK)") (class "Default")
      (node (ref "D31") (pin "K") (pinfunction "K_K") (pintype "passive"))
      (node (ref "R93") (pin "2") (pinfunction "2_2") (pintype "passive"))
    )
    (net (code "49") (name "Net-(D32-PadK)") (class "Default")
      (node (ref "D32") (pin "K") (pinfunction "K_K") (pintype "passive"))
      (node (ref "R94") (pin "2") (pinfunction "2_2") (pintype "passive"))
    )
    (net (code "50") (name "Net-(D33-PadK)") (class "Default")
      (node (ref "D33") (pin "K") (pinfunction "K_K") (pintype "passive"))
      (node (ref "R88") (pin "2") (pinfunction "2_2") (pintype "passive"))
    )
    (net (code "51") (name "Net-(P2-CC1)") (class "Default")
      (node (ref "P2") (pin "A5") (pinfunction "CC1_A5") (pintype "passive"))
      (node (ref "R70") (pin "1") (pinfunction "1_1") (pintype "passive"))
    )
    (net (code "52") (name "Net-(P2-CC2)") (class "Default")
      (node (ref "P2") (pin "B5") (pinfunction "CC2_B5") (pintype "passive"))
      (node (ref "R71") (pin "1") (pinfunction "1_1") (pintype "passive"))
    )
    (net (code "53") (name "Net-(P2-D+1)") (class "Default")
      (node (ref "P2") (pin "A6") (pinfunction "D+1_A6") (pintype "passive"))
      (node (ref "P2") (pin "B6") (pinfunction "D+2_B6") (pintype "passive"))
      (node (ref "R67") (pin "1") (pinfunction "1_1") (pintype "passive"))
    )
    (net (code "54") (name "Net-(P2-D-1)") (class "Default")
      (node (ref "P2") (pin "A7") (pinfunction "D-1_A7") (pintype "passive"))
      (node (ref "P2") (pin "B7") (pinfunction "D-2_B7") (pintype "passive"))
      (node (ref "R68") (pin "1") (pinfunction "1_1") (pintype "passive"))
    )
    (net (code "55") (name "unconnected-(K4-VDD-Pad1)") (class "Default")
      (node (ref "K4") (pin "1") (pinfunction "VDD_1") (pintype "passive"))
    )
    (net (code "56") (name "unconnected-(K4-VDD-Pad3)") (class "Default")
      (node (ref "K4") (pin "3") (pinfunction "VDD_3") (pintype "passive"))
    )
    (net (code "57") (name "unconnected-(P2-SBUS1-PadA8)") (class "Default")
      (node (ref "P2") (pin "A8") (pinfunction "SBUS1_A8") (pintype "passive"))
    )
    (net (code "58") (name "unconnected-(P2-SBUS2-PadB8)") (class "Default")
      (node (ref "P2") (pin "B8") (pinfunction "SBUS2_B8") (pintype "passive"))
    )
    (net (code "59") (name "unconnected-(SERIAL1-Pad2)") (class "Default")
      (node (ref "SERIAL1") (pin "2") (pinfunction "2_2") (pintype "passive"))
    )
    (net (code "60") (name "unconnected-(SERIAL1-Pad6)") (class "Default")
      (node (ref "SERIAL1") (pin "6") (pinfunction "6_6") (pintype "passive"))
    )
    (net (code "61") (name "unconnected-(STLINK1-Pad5)") (class "Default")
      (node (ref "STLINK1") (pin "5") (pinfunction "5_5") (pintype "passive"))
    )
    (net (code "62") (name "unconnected-(U15-(3.3V)_T2C2{slash}MOSI1{slash}SMBAI1{slash}PB5-Pad41)") (class "Default")
      (node (ref "U15") (pin "41") (pinfunction "(3.3V)_T2C2/MOSI1/SMBAI1/PB5_41") (pintype "bidirectional"))
    )
    (net (code "63") (name "unconnected-(U15-PA1{slash}ADC1{slash}RT52{slash}T2C2_(PWM)_(3.3V)-Pad11)") (class "Default")
      (node (ref "U15") (pin "11") (pinfunction "PA1/ADC1/RT52/T2C2_(PWM)_(3.3V)_11") (pintype "bidirectional"))
    )
    (net (code "64") (name "unconnected-(U15-PA4{slash}ADC4{slash}NSS1{slash}CK2_(3.3V)-Pad14)") (class "Default")
      (node (ref "U15") (pin "14") (pinfunction "PA4/ADC4/NSS1/CK2_(3.3V)_14") (pintype "bidirectional"))
    )
    (net (code "65") (name "unconnected-(U15-PA5{slash}ADC5{slash}SCK1_(3.3V)-Pad15)") (class "Default")
      (node (ref "U15") (pin "15") (pinfunction "PA5/ADC5/SCK1_(3.3V)_15") (pintype "bidirectional"))
    )
    (net (code "66") (name "unconnected-(U15-RTS3{slash}T1C2N{slash}MISO2{slash}PB14-Pad27)") (class "Default")
      (node (ref "U15") (pin "27") (pinfunction "RTS3/T1C2N/MISO2/PB14_27") (pintype "bidirectional"))
    )
    (net (code "67") (name "unconnected-(U15-T3C1{slash}MISO1{slash}JTRST{slash}PB4-Pad40)") (class "Default")
      (node (ref "U15") (pin "40") (pinfunction "T3C1/MISO1/JTRST/PB4_40") (pintype "bidirectional"))
    )
  )
)
